# bq76920_IC.net
KiCad netlist of a schematic drawn in Altium Designer
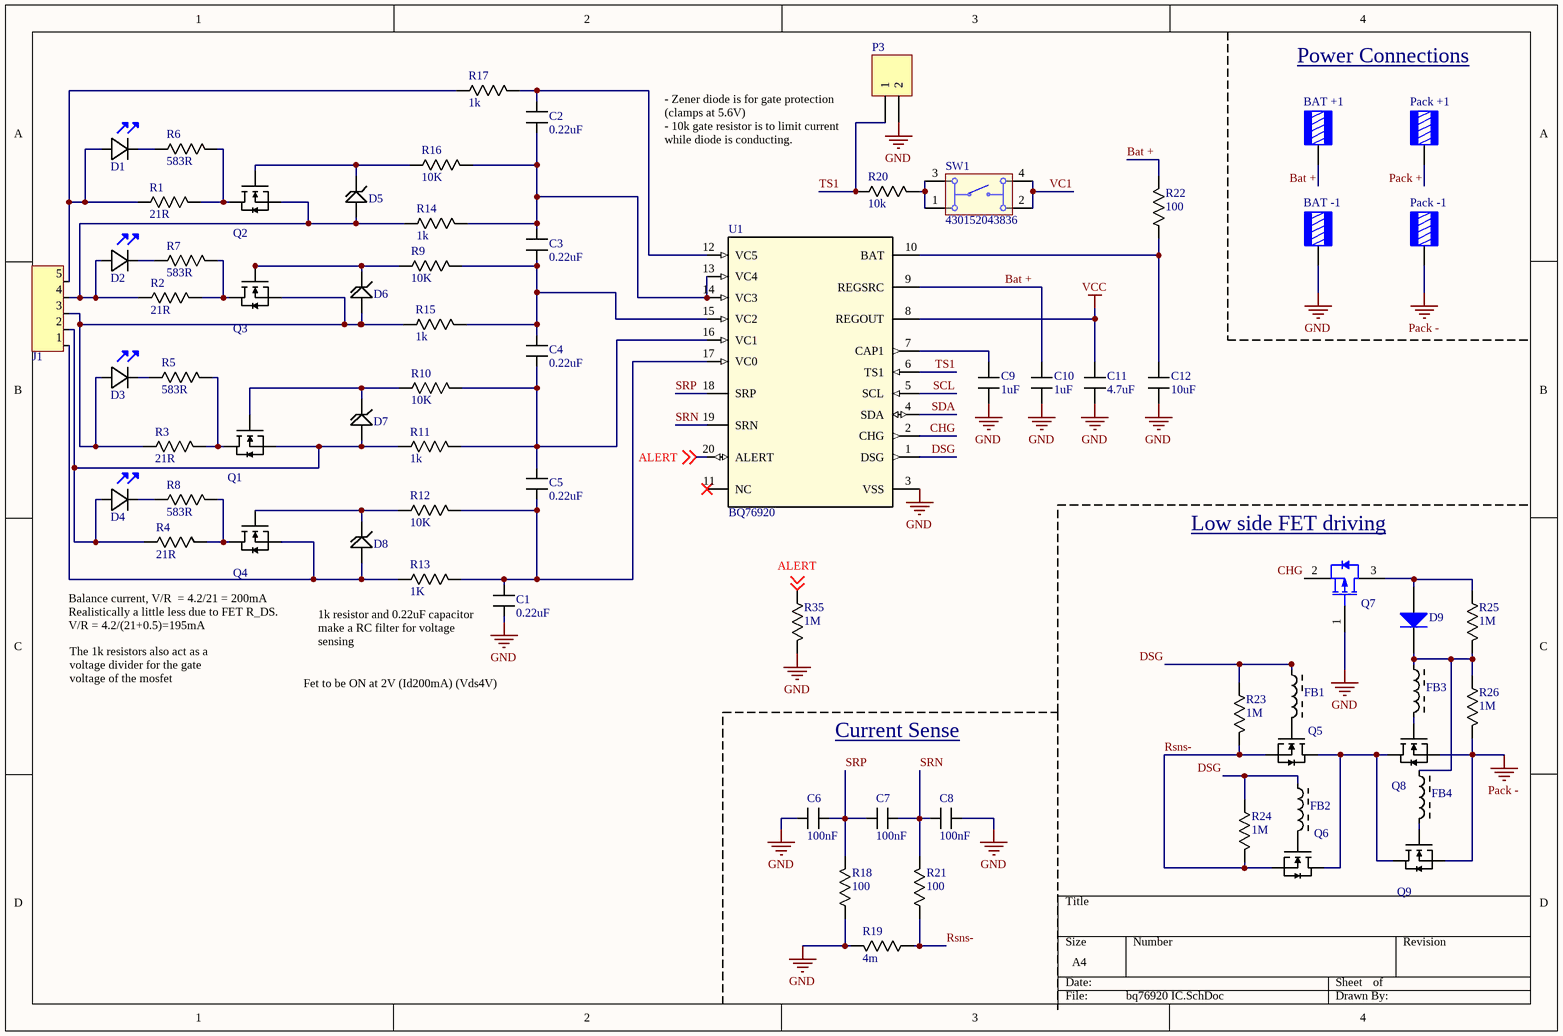
[diagram p0: bq76920 IC.SchDoc]

(export (version "E")
  (design (tool "Eeschema 10.0.6"))
  (components
    (comp (ref "BAT +1")
      (value "7460305")
      (footprint "7460305")
      (description "WP-BUTR Press-Fit with Internal thread, two rows, 9x9mm, 8 pins, M5x6mm, 160A")
      (fields (field (name "PUBLISHER") "Wurth Elektronik"))
      (libsource (lib "7460307_Altium_WP-BUTR_rev19a") (part "7460305"))
    )
    (comp (ref "BAT -1")
      (value "7460305")
      (footprint "7460305")
      (description "WP-BUTR Press-Fit with Internal thread, two rows, 9x9mm, 8 pins, M5x6mm, 160A")
      (fields (field (name "PUBLISHER") "Wurth Elektronik"))
      (libsource (lib "7460307_Altium_WP-BUTR_rev19a") (part "7460305"))
    )
    (comp (ref "C1")
      (value "0.22uF")
      (footprint "C_0603")
      (description "Cap Ceramic 0.22uF 25V X7R 10% Pad SMD 0603 125C Automotive T/R")
      (fields
        (field (name "MANUFACTURER") "KEMET")
        (field (name "MANUFACTURER PART NUMBER") "C0603C224K3RECAUTO")
      )
      (libsource (lib "Passives") (part "Capacitor"))
    )
    (comp (ref "C2")
      (value "0.22uF")
      (footprint "C_0603")
      (description "Cap Ceramic 0.22uF 25V X7R 10% Pad SMD 0603 125C Automotive T/R")
      (fields
        (field (name "MANUFACTURER") "KEMET")
        (field (name "MANUFACTURER PART NUMBER") "C0603C224K3RECAUTO")
      )
      (libsource (lib "Passives") (part "Capacitor"))
    )
    (comp (ref "C3")
      (value "0.22uF")
      (footprint "C_0603")
      (description "Cap Ceramic 0.22uF 25V X7R 10% Pad SMD 0603 125C Automotive T/R")
      (fields
        (field (name "MANUFACTURER") "KEMET")
        (field (name "MANUFACTURER PART NUMBER") "C0603C224K3RECAUTO")
      )
      (libsource (lib "Passives") (part "Capacitor"))
    )
    (comp (ref "C4")
      (value "0.22uF")
      (footprint "C_0603")
      (description "Cap Ceramic 0.22uF 25V X7R 10% Pad SMD 0603 125C Automotive T/R")
      (fields
        (field (name "MANUFACTURER") "KEMET")
        (field (name "MANUFACTURER PART NUMBER") "C0603C224K3RECAUTO")
      )
      (libsource (lib "Passives") (part "Capacitor"))
    )
    (comp (ref "C5")
      (value "0.22uF")
      (footprint "C_0603")
      (description "Cap Ceramic 0.22uF 25V X7R 10% Pad SMD 0603 125C Automotive T/R")
      (fields
        (field (name "MANUFACTURER") "KEMET")
        (field (name "MANUFACTURER PART NUMBER") "C0603C224K3RECAUTO")
      )
      (libsource (lib "Passives") (part "Capacitor"))
    )
    (comp (ref "C6")
      (value "100nF")
      (footprint "C_0603")
      (description "CAP CER 0.1UF 50V X7R 0603")
      (fields
        (field (name "MANUFACTURER") "KEMET")
        (field (name "MANUFACTURER PART NUMBER") "C0603X104K5RAC7411")
      )
      (libsource (lib "Passives") (part "Capacitor"))
    )
    (comp (ref "C7")
      (value "100nF")
      (footprint "C_0603")
      (description "CAP CER 0.1UF 50V X7R 0603")
      (fields
        (field (name "MANUFACTURER") "KEMET")
        (field (name "MANUFACTURER PART NUMBER") "C0603X104K5RAC7411")
      )
      (libsource (lib "Passives") (part "Capacitor"))
    )
    (comp (ref "C8")
      (value "100nF")
      (footprint "C_0603")
      (description "CAP CER 0.1UF 50V X7R 0603")
      (fields
        (field (name "MANUFACTURER") "KEMET")
        (field (name "MANUFACTURER PART NUMBER") "C0603X104K5RAC7411")
      )
      (libsource (lib "Passives") (part "Capacitor"))
    )
    (comp (ref "C9")
      (value "1uF")
      (footprint "C_0603")
      (description "Capacitor")
      (fields
        (field (name "MANUFACTURER") "KEMET")
        (field (name "MANUFACTURER PART NUMBER") "C0603C105K9RAC7411")
      )
      (libsource (lib "") (part "Capacitor_1"))
    )
    (comp (ref "C10")
      (value "1uF")
      (footprint "C_0603")
      (description "Cap Ceramic 1uF 25V X7R 10% Pad SMD 0603 125°C Automotive T/R")
      (fields
        (field (name "MANUFACTURER") "KEMET")
        (field (name "MANUFACTURER PART NUMBER") "C0603C105K9RAC7411")
      )
      (libsource (lib "") (part "Capacitor_1"))
    )
    (comp (ref "C11")
      (value "4.7uF")
      (footprint "C_0603")
      (description "Cap Ceramic 4.7uF 6.3V X7R 10% Pad SMD 0603 125°C T/R")
      (fields
        (field (name "MANUFACTURER") "Taiyo Yuden")
        (field (name "MANUFACTURER PART NUMBER") "JMK107BB7475KA-T")
      )
      (libsource (lib "") (part "Capacitor_1"))
    )
    (comp (ref "C12")
      (value "GRM188R6YA106MA73J")
      (footprint "C_0603")
      (description "CAP CER 10UF X5R 0603")
      (fields
        (field (name "MANUFACTURER") "Murata")
        (field (name "CAPACITANCE") "10uF")
        (field (name "TOLERANCE") "20%")
      )
      (libsource (lib "") (part "Capacitor_1"))
    )
    (comp (ref "D1")
      (value "150060BS55040")
      (footprint "150060xS55040")
      (description "LED BLUE DIFFUSED 0603 SMD")
      (fields (field (name "MANUFACTURER") "Wurth Electronics"))
      (libsource (lib "LV BMS SchLib") (part "150060BS55040"))
    )
    (comp (ref "D2")
      (value "150060BS55040")
      (footprint "150060xS55040")
      (description "LED BLUE DIFFUSED 0603 SMD")
      (fields (field (name "MANUFACTURER") "Wurth Electronics"))
      (libsource (lib "LV BMS SchLib") (part "150060BS55040"))
    )
    (comp (ref "D3")
      (value "150060BS55040")
      (footprint "150060xS55040")
      (description "LED BLUE DIFFUSED 0603 SMD")
      (fields (field (name "MANUFACTURER") "Wurth Electronics"))
      (libsource (lib "LV BMS SchLib") (part "150060BS55040"))
    )
    (comp (ref "D4")
      (value "150060BS55040")
      (footprint "150060xS55040")
      (description "LED BLUE DIFFUSED 0603 SMD")
      (fields (field (name "MANUFACTURER") "Wurth Electronics"))
      (libsource (lib "LV BMS SchLib") (part "150060BS55040"))
    )
    (comp (ref "D5")
      (value "MMSZ5232BS-7-F")
      (footprint "MMSZ5232BS-7-F")
      (description "Balance Diode\r\nMMSZ5232BS-7-F")
      (libsource (lib "BMS_Schem") (part "MMSZ5232BS-7-F"))
    )
    (comp (ref "D6")
      (value "MMSZ5232BS-7-F")
      (footprint "MMSZ5232BS-7-F")
      (description "Balance Diode\r\nMMSZ5232BS-7-F")
      (libsource (lib "BMS_Schem") (part "MMSZ5232BS-7-F"))
    )
    (comp (ref "D7")
      (value "MMSZ5232BS-7-F")
      (footprint "MMSZ5232BS-7-F")
      (description "Balance Diode\r\nMMSZ5232BS-7-F")
      (libsource (lib "BMS_Schem") (part "MMSZ5232BS-7-F"))
    )
    (comp (ref "D8")
      (value "MMSZ5232BS-7-F")
      (footprint "MMSZ5232BS-7-F")
      (description "Balance Diode\r\nMMSZ5232BS-7-F")
      (libsource (lib "BMS_Schem") (part "MMSZ5232BS-7-F"))
    )
    (comp (ref "D9")
      (value "MMDL6050T1G")
      (footprint "ONSC-SOD-323-2-477-02_V")
      (description "Switching Diode, 2-Pin SOD-323, Pb-Free, Tape and Reel")
      (fields (field (name "MANUFACTURER") "On Semiconductor"))
      (libsource (lib "Altium Content Vault") (part "ONSC-D-K1A2-2"))
    )
    (comp (ref "FB1")
      (value "BLM18SG221TN1D")
      (footprint "R-0603")
      (description "FERRITE BEAD 220 OHM 0603 1LN")
      (fields (field (name "MANUFACTURER") "Murata") (field (name "TOLERANCE") "25%"))
      (libsource (lib "LV BMS SchLib") (part "BLM18SG221TN1D"))
    )
    (comp (ref "FB2")
      (value "BLM18SG221TN1D")
      (footprint "R-0603")
      (description "FERRITE BEAD 220 OHM 0603 1LN")
      (fields (field (name "MANUFACTURER") "Murata") (field (name "TOLERANCE") "25%"))
      (libsource (lib "LV BMS SchLib") (part "BLM18SG221TN1D"))
    )
    (comp (ref "FB3")
      (value "BLM18SG221TN1D")
      (footprint "R-0603")
      (description "FERRITE BEAD 220 OHM 0603 1LN")
      (fields (field (name "MANUFACTURER") "Murata") (field (name "TOLERANCE") "25%"))
      (libsource (lib "LV BMS SchLib") (part "BLM18SG221TN1D"))
    )
    (comp (ref "FB4")
      (value "BLM18SG221TN1D")
      (footprint "R-0603")
      (description "FERRITE BEAD 220 OHM 0603 1LN")
      (fields (field (name "MANUFACTURER") "Murata") (field (name "TOLERANCE") "25%"))
      (libsource (lib "LV BMS SchLib") (part "BLM18SG221TN1D"))
    )
    (comp (ref "J1")
      (value "2-1445090-5")
      (footprint "2-1445090-5")
      (fields (field (name "MANUFACTURER") "TE Connectivity"))
      (libsource (lib "LV BMS SchLib") (part "2-1445090-5"))
    )
    (comp (ref "P3")
      (value "For thermistor")
      (footprint "HDR1X2")
      (description "Header, 2-Pin")
      (fields (field (name "PUBLISHER") "Altium Limited"))
      (libsource (lib "Miscellaneous Connectors") (part "Header 2"))
    )
    (comp (ref "Pack +1")
      (value "7460305")
      (footprint "7460305")
      (description "WP-BUTR Press-Fit with Internal thread, two rows, 9x9mm, 8 pins, M5x6mm, 160A")
      (fields (field (name "PUBLISHER") "Wurth Elektronik"))
      (libsource (lib "7460307_Altium_WP-BUTR_rev19a") (part "7460305"))
    )
    (comp (ref "Pack -1")
      (value "7460305")
      (footprint "7460305")
      (description "WP-BUTR Press-Fit with Internal thread, two rows, 9x9mm, 8 pins, M5x6mm, 160A")
      (fields (field (name "PUBLISHER") "Wurth Elektronik"))
      (libsource (lib "7460307_Altium_WP-BUTR_rev19a") (part "7460305"))
    )
    (comp (ref "Q1")
      (value "DMG1012T-13")
      (footprint "SOT-523-3")
      (description "Trans Mosfet N-ch 20V 0.63A 3-PIN SOT-523 T/r")
      (fields (field (name "MANUFACTURER") "Diodes"))
      (libsource (lib "LV BMS SchLib") (part "DMG1012T-13"))
    )
    (comp (ref "Q2")
      (value "DMG1012T-13")
      (footprint "SOT-523-3")
      (description "Trans Mosfet N-ch 20V 0.63A 3-PIN SOT-523 T/r")
      (fields (field (name "MANUFACTURER") "Diodes"))
      (libsource (lib "LV BMS SchLib") (part "DMG1012T-13"))
    )
    (comp (ref "Q3")
      (value "DMG1012T-13")
      (footprint "SOT-523-3")
      (description "Trans Mosfet N-ch 20V 0.63A 3-PIN SOT-523 T/r")
      (fields (field (name "MANUFACTURER") "Diodes"))
      (libsource (lib "LV BMS SchLib") (part "DMG1012T-13"))
    )
    (comp (ref "Q4")
      (value "DMG1012T-13")
      (footprint "SOT-523-3")
      (description "Trans Mosfet N-ch 20V 0.63A 3-PIN SOT-523 T/r")
      (fields (field (name "MANUFACTURER") "Diodes"))
      (libsource (lib "LV BMS SchLib") (part "DMG1012T-13"))
    )
    (comp (ref "Q5")
      (value "TK25S06N1L,LXHQ")
      (footprint "DPAK+")
      (description "MOSFET 57W 1MHz Automotive; AEC-Q101")
      (fields
        (field (name "MANUFACTURER PART NUMBER") "TK25S06N1L,LQ(O")
        (field (name "MANUFACTURER") "Toshiba")
      )
      (libsource (lib "LV BMS SchLib") (part "TK25S06N1L,LXHQ"))
    )
    (comp (ref "Q6")
      (value "TK25S06N1L,LXHQ")
      (footprint "DPAK+")
      (description "MOSFET 57W 1MHz Automotive; AEC-Q101")
      (fields
        (field (name "MANUFACTURER PART NUMBER") "TK25S06N1L,LQ(O")
        (field (name "MANUFACTURER") "Toshiba")
      )
      (libsource (lib "LV BMS SchLib") (part "TK25S06N1L,LXHQ"))
    )
    (comp (ref "Q7")
      (value "FDN5618P")
      (footprint "FAIR-SSOT3L-3_V")
      (description "P-Channel Logic Level PowerTrench(R) MOSFET, -60 V, -1.25 A, 3-Pin SOT23, RoHS, Tape and Reel")
      (fields (field (name "MANUFACTURER") "Fairchild Semiconductor"))
      (libsource (lib "Altium Content Vault") (part "PEMOS-GSD-3"))
    )
    (comp (ref "Q8")
      (value "TK25S06N1L,LXHQ")
      (footprint "DPAK+")
      (description "MOSFET 57W 1MHz Automotive; AEC-Q101")
      (fields
        (field (name "MANUFACTURER PART NUMBER") "TK25S06N1L,LQ(O")
        (field (name "MANUFACTURER") "Toshiba")
      )
      (libsource (lib "LV BMS SchLib") (part "TK25S06N1L,LXHQ"))
    )
    (comp (ref "Q9")
      (value "TK25S06N1L,LXHQ")
      (footprint "DPAK+")
      (description "MOSFET 57W 1MHz Automotive; AEC-Q101")
      (fields
        (field (name "MANUFACTURER PART NUMBER") "TK25S06N1L,LQ(O")
        (field (name "MANUFACTURER") "Toshiba")
      )
      (libsource (lib "LV BMS SchLib") (part "TK25S06N1L,LXHQ"))
    )
    (comp (ref "R1")
      (value "21R")
      (footprint "R_2512")
      (description "RES SMD 21 OHM 1% 1.5W 2512")
      (fields
        (field (name "MANUFACTURER") "Vishay Dale")
        (field (name "MANUFACTURER PART NUMBER") "CRCW251221R0FKEGHP")
      )
      (libsource (lib "Passives") (part "Resistor"))
    )
    (comp (ref "R2")
      (value "21R")
      (footprint "R_2512")
      (description "RES SMD 21 OHM 1% 1.5W 2512")
      (fields
        (field (name "MANUFACTURER") "Vishay Dale")
        (field (name "MANUFACTURER PART NUMBER") "CRCW251221R0FKEGHP")
      )
      (libsource (lib "Passives") (part "Resistor"))
    )
    (comp (ref "R3")
      (value "21R")
      (footprint "R_2512")
      (description "RES SMD 21 OHM 1% 1.5W 2512")
      (fields
        (field (name "MANUFACTURER") "Vishay Dale")
        (field (name "MANUFACTURER PART NUMBER") "CRCW251221R0FKEGHP")
      )
      (libsource (lib "Passives") (part "Resistor"))
    )
    (comp (ref "R4")
      (value "21R")
      (footprint "R_2512")
      (description "RES SMD 21 OHM 1% 1.5W 2512")
      (fields
        (field (name "MANUFACTURER") "Vishay Dale")
        (field (name "MANUFACTURER PART NUMBER") "CRCW251221R0FKEGHP")
      )
      (libsource (lib "Passives") (part "Resistor"))
    )
    (comp (ref "R5")
      (value "583R")
      (footprint "R-0603")
      (description "High Precision-High Stability Chip Resistor Thin Film 0603 583Ohm 0.5% Paper T/R")
      (fields
        (field (name "MANUFACTURER") "Yageo")
        (field (name "MANUFACTURER PART NUMBER") "RT0603DRE07583RL")
      )
      (libsource (lib "Passives") (part "Resistor"))
    )
    (comp (ref "R6")
      (value "583R")
      (footprint "R-0603")
      (description "High Precision-High Stability Chip Resistor Thin Film 0603 583Ohm 0.5% Paper T/R")
      (fields
        (field (name "MANUFACTURER") "Yageo")
        (field (name "MANUFACTURER PART NUMBER") "RT0603DRE07583RL")
      )
      (libsource (lib "Passives") (part "Resistor"))
    )
    (comp (ref "R7")
      (value "583R")
      (footprint "R-0603")
      (description "High Precision-High Stability Chip Resistor Thin Film 0603 583Ohm 0.5% Paper T/R")
      (fields
        (field (name "MANUFACTURER") "Yageo")
        (field (name "MANUFACTURER PART NUMBER") "RT0603DRE07583RL")
      )
      (libsource (lib "Passives") (part "Resistor"))
    )
    (comp (ref "R8")
      (value "583R")
      (footprint "R-0603")
      (description "High Precision-High Stability Chip Resistor Thin Film 0603 583Ohm 0.5% Paper T/R")
      (fields
        (field (name "MANUFACTURER") "Yageo")
        (field (name "MANUFACTURER PART NUMBER") "RT0603DRE07583RL")
      )
      (libsource (lib "Passives") (part "Resistor"))
    )
    (comp (ref "R9")
      (value "10K")
      (footprint "R-0603")
      (description "Resistor")
      (fields
        (field (name "MANUFACTURER") "Bourns")
        (field (name "MANUFACTURER PART NUMBER") "CMP0603AFX-1002ELF")
      )
      (libsource (lib "Passives") (part "Resistor"))
    )
    (comp (ref "R10")
      (value "10K")
      (footprint "R-0603")
      (description "Resistor")
      (fields
        (field (name "MANUFACTURER") "Bourns")
        (field (name "MANUFACTURER PART NUMBER") "CMP0603AFX-1002ELF")
      )
      (libsource (lib "Passives") (part "Resistor"))
    )
    (comp (ref "R11")
      (value "1k")
      (footprint "R-0603")
      (fields
        (field (name "MANUFACTURER") "Vishay Dale")
        (field (name "MANUFACTURER PART NUMBER") "CRCW06031K00FKEA")
        (field (name "TOLERANCE") "1%")
      )
      (libsource (lib "Passives") (part "Resistor"))
    )
    (comp (ref "R12")
      (value "10K")
      (footprint "R-0603")
      (description "Resistor")
      (fields
        (field (name "MANUFACTURER") "Bourns")
        (field (name "MANUFACTURER PART NUMBER") "CMP0603AFX-1002ELF")
      )
      (libsource (lib "Passives") (part "Resistor"))
    )
    (comp (ref "R13")
      (value "1K")
      (footprint "R-0603")
      (fields
        (field (name "MANUFACTURER") "Vishay Dale")
        (field (name "MANUFACTURER PART NUMBER") "CRCW06031K00FKEA")
        (field (name "TOLERANCE") "1%")
      )
      (libsource (lib "Passives") (part "Resistor"))
    )
    (comp (ref "R14")
      (value "1k")
      (footprint "R-0603")
      (fields
        (field (name "MANUFACTURER") "Vishay Dale")
        (field (name "MANUFACTURER PART NUMBER") "CRCW06031K00FKEA")
        (field (name "TOLERANCE") "1%")
      )
      (libsource (lib "Passives") (part "Resistor"))
    )
    (comp (ref "R15")
      (value "1k")
      (footprint "R-0603")
      (fields
        (field (name "MANUFACTURER") "Vishay Dale")
        (field (name "MANUFACTURER PART NUMBER") "CRCW06031K00FKEA")
        (field (name "TOLERANCE") "1%")
      )
      (libsource (lib "Passives") (part "Resistor"))
    )
    (comp (ref "R16")
      (value "10K")
      (footprint "R-0603")
      (description "Resistor")
      (fields
        (field (name "MANUFACTURER") "Bourns")
        (field (name "MANUFACTURER PART NUMBER") "CMP0603AFX-1002ELF")
      )
      (libsource (lib "Passives") (part "Resistor"))
    )
    (comp (ref "R17")
      (value "1k")
      (footprint "R-0603")
      (fields
        (field (name "MANUFACTURER") "Vishay Dale")
        (field (name "MANUFACTURER PART NUMBER") "CRCW06031K00FKEA")
        (field (name "TOLERANCE") "1%")
      )
      (libsource (lib "Passives") (part "Resistor"))
    )
    (comp (ref "R18")
      (value "100")
      (footprint "R-0603")
      (description "Resistor")
      (fields
        (field (name "MANUFACTURER") "KOA Speer")
        (field (name "MANUFACTURER PART NUMBER") "RN73R1JTTD1000F50")
      )
      (libsource (lib "Passives") (part "Resistor"))
    )
    (comp (ref "R19")
      (value "4m")
      (footprint "PU3921FKM130R004L")
      (description "Res Metal Plate 3921 0.004 Ohm 1% 3W ±75ppm/C Pad SMD Automotive T/R")
      (fields
        (field (name "MANUFACTURER") "Yageo")
        (field (name "MANUFACTURER PART NUMBER") "PU3921FKM130R004L")
      )
      (libsource (lib "Passives") (part "Resistor"))
    )
    (comp (ref "R20")
      (value "10k")
      (footprint "R-0603")
      (description "Resistor")
      (fields
        (field (name "MANUFACTURER") "Bourns")
        (field (name "MANUFACTURER PART NUMBER") "CMP0603AFX-1002ELF")
      )
      (libsource (lib "Passives") (part "Resistor"))
    )
    (comp (ref "R21")
      (value "100")
      (footprint "R-0603")
      (description "Resistor")
      (fields
        (field (name "MANUFACTURER") "KOA Speer")
        (field (name "MANUFACTURER PART NUMBER") "RN73R1JTTD1000F50")
      )
      (libsource (lib "Passives") (part "Resistor"))
    )
    (comp (ref "R22")
      (value "100")
      (footprint "R-0603")
      (description "Resistor")
      (fields
        (field (name "MANUFACTURER") "KOA Speer")
        (field (name "MANUFACTURER PART NUMBER") "RN73R1JTTD1000F50")
      )
      (libsource (lib "Passives") (part "Resistor"))
    )
    (comp (ref "R23")
      (value "1M")
      (footprint "R-0603")
      (description "Resistor")
      (fields
        (field (name "MANUFACTURER") "Vishay")
        (field (name "MANUFACTURER PART NUMBER") "CRCW06031M00FKEAC")
      )
      (libsource (lib "Passives") (part "Resistor"))
    )
    (comp (ref "R24")
      (value "1M")
      (footprint "R-0603")
      (description "Resistor")
      (fields
        (field (name "MANUFACTURER") "Vishay")
        (field (name "MANUFACTURER PART NUMBER") "CRCW06031M00FKEAC")
      )
      (libsource (lib "Passives") (part "Resistor"))
    )
    (comp (ref "R25")
      (value "1M")
      (footprint "R-0603")
      (description "Resistor")
      (fields
        (field (name "MANUFACTURER") "Vishay")
        (field (name "MANUFACTURER PART NUMBER") "CRCW06031M00FKEAC")
      )
      (libsource (lib "Passives") (part "Resistor"))
    )
    (comp (ref "R26")
      (value "1M")
      (footprint "R-0603")
      (description "Resistor")
      (fields
        (field (name "MANUFACTURER") "Vishay")
        (field (name "MANUFACTURER PART NUMBER") "CRCW06031M00FKEAC")
      )
      (libsource (lib "Passives") (part "Resistor"))
    )
    (comp (ref "R35")
      (value "1M")
      (footprint "R-0603")
      (description "Resistor")
      (fields
        (field (name "MANUFACTURER") "Vishay")
        (field (name "MANUFACTURER PART NUMBER") "CRCW06031M00FKEAC")
      )
      (libsource (lib "Passives") (part "Resistor"))
    )
    (comp (ref "SW1")
      (value "430152043836")
      (footprint "430152043836")
      (description "WS-TASV SMD Tact Switch 6X6 mm")
      (fields (field (name "MANUFACTURER") "Wuerth Elektronik"))
      (libsource (lib "Altium Content Vault") (part "WE-TACT-SW-4"))
    )
    (comp (ref "U1")
      (value "BQ76920")
      (footprint "TSSOP-20")
      (description "3 to 5-Series Cell Li-Ion and Li-Phosphate Battery Monitor")
      (fields
        (field (name "MANUFACTURER") "Texas Instruments")
        (field (name "MANUFACTURER PART NUMBER") "BQ7692003PWR")
      )
      (libsource (lib "LV BMS SchLib") (part "BQ76920"))
    )
  )
  (nets
    (net (code "1") (name "/Bat +") (class "Default")
      (node (ref "BAT +1") (pin "1") (pinfunction "1_1") (pintype "passive"))
      (node (ref "C10") (pin "2") (pinfunction "2_2") (pintype "passive"))
      (node (ref "R22") (pin "2") (pinfunction "2_2") (pintype "passive"))
      (node (ref "U1") (pin "9") (pinfunction "REGSRC_9") (pintype "power_in"))
    )
    (net (code "2") (name "/CHG") (class "Default")
      (node (ref "Q7") (pin "2") (pinfunction "SOURCE_2") (pintype "passive"))
      (node (ref "U1") (pin "2") (pinfunction "CHG_2") (pintype "output"))
    )
    (net (code "3") (name "/DSG") (class "Default")
      (node (ref "FB1") (pin "2") (pintype "passive"))
      (node (ref "FB2") (pin "2") (pintype "passive"))
      (node (ref "R23") (pin "1") (pinfunction "1_1") (pintype "passive"))
      (node (ref "R24") (pin "1") (pinfunction "1_1") (pintype "passive"))
      (node (ref "U1") (pin "1") (pinfunction "DSG_1") (pintype "output"))
    )
    (net (code "4") (name "/Pack +") (class "Default")
      (node (ref "Pack +1") (pin "1") (pinfunction "1_1") (pintype "passive"))
    )
    (net (code "5") (name "/Rsns-") (class "Default")
      (node (ref "Q5") (pin "3") (pinfunction "Source_3") (pintype "passive"))
      (node (ref "Q6") (pin "3") (pinfunction "Source_3") (pintype "passive"))
      (node (ref "R19") (pin "1") (pinfunction "1_1") (pintype "passive"))
      (node (ref "R21") (pin "1") (pinfunction "1_1") (pintype "passive"))
      (node (ref "R23") (pin "2") (pinfunction "2_2") (pintype "passive"))
      (node (ref "R24") (pin "2") (pinfunction "2_2") (pintype "passive"))
    )
    (net (code "6") (name "/SCL") (class "Default")
      (node (ref "U1") (pin "5") (pinfunction "SCL_5") (pintype "input"))
    )
    (net (code "7") (name "/SDA") (class "Default")
      (node (ref "U1") (pin "4") (pinfunction "SDA_4") (pintype "bidirectional"))
    )
    (net (code "8") (name "/SRN") (class "Default")
      (node (ref "C7") (pin "1") (pinfunction "1_1") (pintype "passive"))
      (node (ref "C8") (pin "2") (pinfunction "2_2") (pintype "passive"))
      (node (ref "R21") (pin "2") (pinfunction "2_2") (pintype "passive"))
      (node (ref "U1") (pin "19") (pinfunction "SRN_19") (pintype "passive"))
    )
    (net (code "9") (name "/SRP") (class "Default")
      (node (ref "C6") (pin "1") (pinfunction "1_1") (pintype "passive"))
      (node (ref "C7") (pin "2") (pinfunction "2_2") (pintype "passive"))
      (node (ref "R18") (pin "2") (pinfunction "2_2") (pintype "passive"))
      (node (ref "U1") (pin "18") (pinfunction "SRP_18") (pintype "passive"))
    )
    (net (code "10") (name "/TS1") (class "Default")
      (node (ref "P3") (pin "1") (pinfunction "1_1") (pintype "passive"))
      (node (ref "R20") (pin "1") (pinfunction "1_1") (pintype "passive"))
      (node (ref "U1") (pin "6") (pinfunction "TS1_6") (pintype "input"))
    )
    (net (code "11") (name "/VC1") (class "Default")
      (node (ref "SW1") (pin "2") (pinfunction "2_2") (pintype "passive"))
      (node (ref "SW1") (pin "4") (pinfunction "4_4") (pintype "passive"))
    )
    (net (code "12") (name "ALERT") (class "Default")
      (node (ref "R35") (pin "1") (pinfunction "1_1") (pintype "passive"))
      (node (ref "U1") (pin "20") (pinfunction "ALERT_20") (pintype "bidirectional"))
    )
    (net (code "13") (name "GND") (class "Default")
      (node (ref "BAT -1") (pin "1") (pinfunction "1_1") (pintype "passive"))
      (node (ref "C1") (pin "1") (pinfunction "1_1") (pintype "passive"))
      (node (ref "C10") (pin "1") (pinfunction "1_1") (pintype "passive"))
      (node (ref "C11") (pin "1") (pinfunction "1_1") (pintype "passive"))
      (node (ref "C12") (pin "1") (pinfunction "1_1") (pintype "passive"))
      (node (ref "C6") (pin "2") (pinfunction "2_2") (pintype "passive"))
      (node (ref "C8") (pin "1") (pinfunction "1_1") (pintype "passive"))
      (node (ref "C9") (pin "1") (pinfunction "1_1") (pintype "passive"))
      (node (ref "P3") (pin "2") (pinfunction "2_2") (pintype "passive"))
      (node (ref "Q7") (pin "1") (pinfunction "GATE_1") (pintype "passive"))
      (node (ref "R18") (pin "1") (pinfunction "1_1") (pintype "passive"))
      (node (ref "R19") (pin "2") (pinfunction "2_2") (pintype "passive"))
      (node (ref "R35") (pin "2") (pinfunction "2_2") (pintype "passive"))
      (node (ref "U1") (pin "3") (pinfunction "VSS_3") (pintype "power_in"))
    )
    (net (code "14") (name "Net-(D1-Anode)") (class "Default")
      (node (ref "D1") (pin "2") (pinfunction "Anode_2") (pintype "passive"))
      (node (ref "J1") (pin "5") (pintype "passive"))
      (node (ref "R1") (pin "1") (pinfunction "1_1") (pintype "passive"))
      (node (ref "R17") (pin "1") (pinfunction "1_1") (pintype "passive"))
    )
    (net (code "15") (name "Net-(D1-Cathode)") (class "Default")
      (node (ref "D1") (pin "1") (pinfunction "Cathode_1") (pintype "passive"))
      (node (ref "R6") (pin "1") (pinfunction "1_1") (pintype "passive"))
    )
    (net (code "16") (name "Net-(D2-Anode)") (class "Default")
      (node (ref "D2") (pin "2") (pinfunction "Anode_2") (pintype "passive"))
      (node (ref "D5") (pin "2") (pinfunction "Anode_(+)_2") (pintype "passive"))
      (node (ref "J1") (pin "4") (pintype "passive"))
      (node (ref "Q2") (pin "2") (pinfunction "Source_2") (pintype "passive"))
      (node (ref "R14") (pin "1") (pinfunction "1_1") (pintype "passive"))
      (node (ref "R2") (pin "1") (pinfunction "1_1") (pintype "passive"))
    )
    (net (code "17") (name "Net-(D2-Cathode)") (class "Default")
      (node (ref "D2") (pin "1") (pinfunction "Cathode_1") (pintype "passive"))
      (node (ref "R7") (pin "1") (pinfunction "1_1") (pintype "passive"))
    )
    (net (code "18") (name "Net-(D3-Anode)") (class "Default")
      (node (ref "D3") (pin "2") (pinfunction "Anode_2") (pintype "passive"))
      (node (ref "D6") (pin "2") (pinfunction "Anode_(+)_2") (pintype "passive"))
      (node (ref "J1") (pin "3") (pintype "passive"))
      (node (ref "Q3") (pin "2") (pinfunction "Source_2") (pintype "passive"))
      (node (ref "R15") (pin "1") (pinfunction "1_1") (pintype "passive"))
      (node (ref "R3") (pin "1") (pinfunction "1_1") (pintype "passive"))
    )
    (net (code "19") (name "Net-(D3-Cathode)") (class "Default")
      (node (ref "D3") (pin "1") (pinfunction "Cathode_1") (pintype "passive"))
      (node (ref "R5") (pin "1") (pinfunction "1_1") (pintype "passive"))
    )
    (net (code "20") (name "Net-(D4-Anode)") (class "Default")
      (node (ref "D4") (pin "2") (pinfunction "Anode_2") (pintype "passive"))
      (node (ref "D7") (pin "2") (pinfunction "Anode_(+)_2") (pintype "passive"))
      (node (ref "J1") (pin "2") (pintype "passive"))
      (node (ref "Q1") (pin "2") (pinfunction "Source_2") (pintype "passive"))
      (node (ref "R11") (pin "1") (pinfunction "1_1") (pintype "passive"))
      (node (ref "R4") (pin "1") (pinfunction "1_1") (pintype "passive"))
    )
    (net (code "21") (name "Net-(D4-Cathode)") (class "Default")
      (node (ref "D4") (pin "1") (pinfunction "Cathode_1") (pintype "passive"))
      (node (ref "R8") (pin "1") (pinfunction "1_1") (pintype "passive"))
    )
    (net (code "22") (name "Net-(D5-Cathode_(-))") (class "Default")
      (node (ref "D5") (pin "1") (pinfunction "Cathode_(-)_1") (pintype "passive"))
      (node (ref "Q2") (pin "1") (pinfunction "Gate_1") (pintype "passive"))
      (node (ref "R16") (pin "1") (pinfunction "1_1") (pintype "passive"))
    )
    (net (code "23") (name "Net-(D6-Cathode_(-))") (class "Default")
      (node (ref "D6") (pin "1") (pinfunction "Cathode_(-)_1") (pintype "passive"))
      (node (ref "Q3") (pin "1") (pinfunction "Gate_1") (pintype "passive"))
      (node (ref "R9") (pin "1") (pinfunction "1_1") (pintype "passive"))
    )
    (net (code "24") (name "Net-(D7-Cathode_(-))") (class "Default")
      (node (ref "D7") (pin "1") (pinfunction "Cathode_(-)_1") (pintype "passive"))
      (node (ref "Q1") (pin "1") (pinfunction "Gate_1") (pintype "passive"))
      (node (ref "R10") (pin "1") (pinfunction "1_1") (pintype "passive"))
    )
    (net (code "25") (name "Net-(D8-Anode_(+))") (class "Default")
      (node (ref "D8") (pin "2") (pinfunction "Anode_(+)_2") (pintype "passive"))
      (node (ref "J1") (pin "1") (pintype "passive"))
      (node (ref "Q4") (pin "2") (pinfunction "Source_2") (pintype "passive"))
      (node (ref "R13") (pin "1") (pinfunction "1_1") (pintype "passive"))
    )
    (net (code "26") (name "Net-(D8-Cathode_(-))") (class "Default")
      (node (ref "D8") (pin "1") (pinfunction "Cathode_(-)_1") (pintype "passive"))
      (node (ref "Q4") (pin "1") (pinfunction "Gate_1") (pintype "passive"))
      (node (ref "R12") (pin "1") (pinfunction "1_1") (pintype "passive"))
    )
    (net (code "27") (name "Net-(D9-A)") (class "Default")
      (node (ref "D9") (pin "2") (pinfunction "A_2") (pintype "passive"))
      (node (ref "Q7") (pin "3") (pinfunction "DRAIN_3") (pintype "passive"))
      (node (ref "R25") (pin "1") (pinfunction "1_1") (pintype "passive"))
    )
    (net (code "28") (name "Net-(D9-K)") (class "Default")
      (node (ref "D9") (pin "1") (pinfunction "K_1") (pintype "passive"))
      (node (ref "FB3") (pin "2") (pintype "passive"))
      (node (ref "FB4") (pin "2") (pintype "passive"))
      (node (ref "R25") (pin "2") (pinfunction "2_2") (pintype "passive"))
      (node (ref "R26") (pin "1") (pinfunction "1_1") (pintype "passive"))
    )
    (net (code "29") (name "Net-(Q1-Drain)") (class "Default")
      (node (ref "Q1") (pin "3") (pinfunction "Drain_3") (pintype "passive"))
      (node (ref "R3") (pin "2") (pinfunction "2_2") (pintype "passive"))
      (node (ref "R5") (pin "2") (pinfunction "2_2") (pintype "passive"))
    )
    (net (code "30") (name "Net-(Q2-Drain)") (class "Default")
      (node (ref "Q2") (pin "3") (pinfunction "Drain_3") (pintype "passive"))
      (node (ref "R1") (pin "2") (pinfunction "2_2") (pintype "passive"))
      (node (ref "R6") (pin "2") (pinfunction "2_2") (pintype "passive"))
    )
    (net (code "31") (name "Net-(Q3-Drain)") (class "Default")
      (node (ref "Q3") (pin "3") (pinfunction "Drain_3") (pintype "passive"))
      (node (ref "R2") (pin "2") (pinfunction "2_2") (pintype "passive"))
      (node (ref "R7") (pin "2") (pinfunction "2_2") (pintype "passive"))
    )
    (net (code "32") (name "Net-(Q4-Drain)") (class "Default")
      (node (ref "Q4") (pin "3") (pinfunction "Drain_3") (pintype "passive"))
      (node (ref "R4") (pin "2") (pinfunction "2_2") (pintype "passive"))
      (node (ref "R8") (pin "2") (pinfunction "2_2") (pintype "passive"))
    )
    (net (code "33") (name "Net-(Q5-Drain)") (class "Default")
      (node (ref "Q5") (pin "2") (pinfunction "Drain_2") (pintype "passive"))
      (node (ref "Q6") (pin "2") (pinfunction "Drain_2") (pintype "passive"))
      (node (ref "Q8") (pin "2") (pinfunction "Drain_2") (pintype "passive"))
      (node (ref "Q9") (pin "2") (pinfunction "Drain_2") (pintype "passive"))
    )
    (net (code "34") (name "Net-(Q5-Gate)") (class "Default")
      (node (ref "FB1") (pin "1") (pintype "passive"))
      (node (ref "Q5") (pin "1") (pinfunction "Gate_1") (pintype "passive"))
    )
    (net (code "35") (name "Net-(Q6-Gate)") (class "Default")
      (node (ref "FB2") (pin "1") (pintype "passive"))
      (node (ref "Q6") (pin "1") (pinfunction "Gate_1") (pintype "passive"))
    )
    (net (code "36") (name "Net-(Q8-Gate)") (class "Default")
      (node (ref "FB3") (pin "1") (pintype "passive"))
      (node (ref "Q8") (pin "1") (pinfunction "Gate_1") (pintype "passive"))
    )
    (net (code "37") (name "Net-(Q9-Gate)") (class "Default")
      (node (ref "FB4") (pin "1") (pintype "passive"))
      (node (ref "Q9") (pin "1") (pinfunction "Gate_1") (pintype "passive"))
    )
    (net (code "38") (name "Net-(R20-Pad2)") (class "Default")
      (node (ref "R20") (pin "2") (pinfunction "2_2") (pintype "passive"))
      (node (ref "SW1") (pin "1") (pinfunction "1_1") (pintype "passive"))
      (node (ref "SW1") (pin "3") (pinfunction "3_3") (pintype "passive"))
    )
    (net (code "39") (name "Net-(U1-BAT)") (class "Default")
      (node (ref "C12") (pin "2") (pinfunction "2_2") (pintype "passive"))
      (node (ref "R22") (pin "1") (pinfunction "1_1") (pintype "passive"))
      (node (ref "U1") (pin "10") (pinfunction "BAT_10") (pintype "power_in"))
    )
    (net (code "40") (name "Net-(U1-CAP1)") (class "Default")
      (node (ref "C9") (pin "2") (pinfunction "2_2") (pintype "passive"))
      (node (ref "U1") (pin "7") (pinfunction "CAP1_7") (pintype "output"))
    )
    (net (code "41") (name "Net-(U1-VC0)") (class "Default")
      (node (ref "C1") (pin "2") (pinfunction "2_2") (pintype "passive"))
      (node (ref "C5") (pin "1") (pinfunction "1_1") (pintype "passive"))
      (node (ref "R12") (pin "2") (pinfunction "2_2") (pintype "passive"))
      (node (ref "R13") (pin "2") (pinfunction "2_2") (pintype "passive"))
      (node (ref "U1") (pin "17") (pinfunction "VC0_17") (pintype "input"))
    )
    (net (code "42") (name "Net-(U1-VC1)") (class "Default")
      (node (ref "C4") (pin "1") (pinfunction "1_1") (pintype "passive"))
      (node (ref "C5") (pin "2") (pinfunction "2_2") (pintype "passive"))
      (node (ref "R10") (pin "2") (pinfunction "2_2") (pintype "passive"))
      (node (ref "R11") (pin "2") (pinfunction "2_2") (pintype "passive"))
      (node (ref "U1") (pin "16") (pinfunction "VC1_16") (pintype "input"))
    )
    (net (code "43") (name "Net-(U1-VC2)") (class "Default")
      (node (ref "C3") (pin "1") (pinfunction "1_1") (pintype "passive"))
      (node (ref "C4") (pin "2") (pinfunction "2_2") (pintype "passive"))
      (node (ref "R15") (pin "2") (pinfunction "2_2") (pintype "passive"))
      (node (ref "R9") (pin "2") (pinfunction "2_2") (pintype "passive"))
      (node (ref "U1") (pin "15") (pinfunction "VC2_15") (pintype "input"))
    )
    (net (code "44") (name "Net-(U1-VC3)") (class "Default")
      (node (ref "C2") (pin "1") (pinfunction "1_1") (pintype "passive"))
      (node (ref "C3") (pin "2") (pinfunction "2_2") (pintype "passive"))
      (node (ref "R14") (pin "2") (pinfunction "2_2") (pintype "passive"))
      (node (ref "R16") (pin "2") (pinfunction "2_2") (pintype "passive"))
      (node (ref "U1") (pin "13") (pinfunction "VC4_13") (pintype "input"))
      (node (ref "U1") (pin "14") (pinfunction "VC3_14") (pintype "input"))
    )
    (net (code "45") (name "Net-(U1-VC5)") (class "Default")
      (node (ref "C2") (pin "2") (pinfunction "2_2") (pintype "passive"))
      (node (ref "R17") (pin "2") (pinfunction "2_2") (pintype "passive"))
      (node (ref "U1") (pin "12") (pinfunction "VC5_12") (pintype "input"))
    )
    (net (code "46") (name "Pack -") (class "Default")
      (node (ref "Pack -1") (pin "1") (pinfunction "1_1") (pintype "passive"))
      (node (ref "Q8") (pin "3") (pinfunction "Source_3") (pintype "passive"))
      (node (ref "Q9") (pin "3") (pinfunction "Source_3") (pintype "passive"))
      (node (ref "R26") (pin "2") (pinfunction "2_2") (pintype "passive"))
    )
    (net (code "47") (name "VCC") (class "Default")
      (node (ref "C11") (pin "2") (pinfunction "2_2") (pintype "passive"))
      (node (ref "U1") (pin "8") (pinfunction "REGOUT_8") (pintype "power_in"))
    )
    (net (code "48") (name "unconnected-(U1-NC-Pad11)") (class "Default")
      (node (ref "U1") (pin "11") (pinfunction "NC_11") (pintype "passive+no_connect"))
    )
  )
)
